# Baseline_Shield.net
KiCad netlist of a schematic drawn in EAGLE
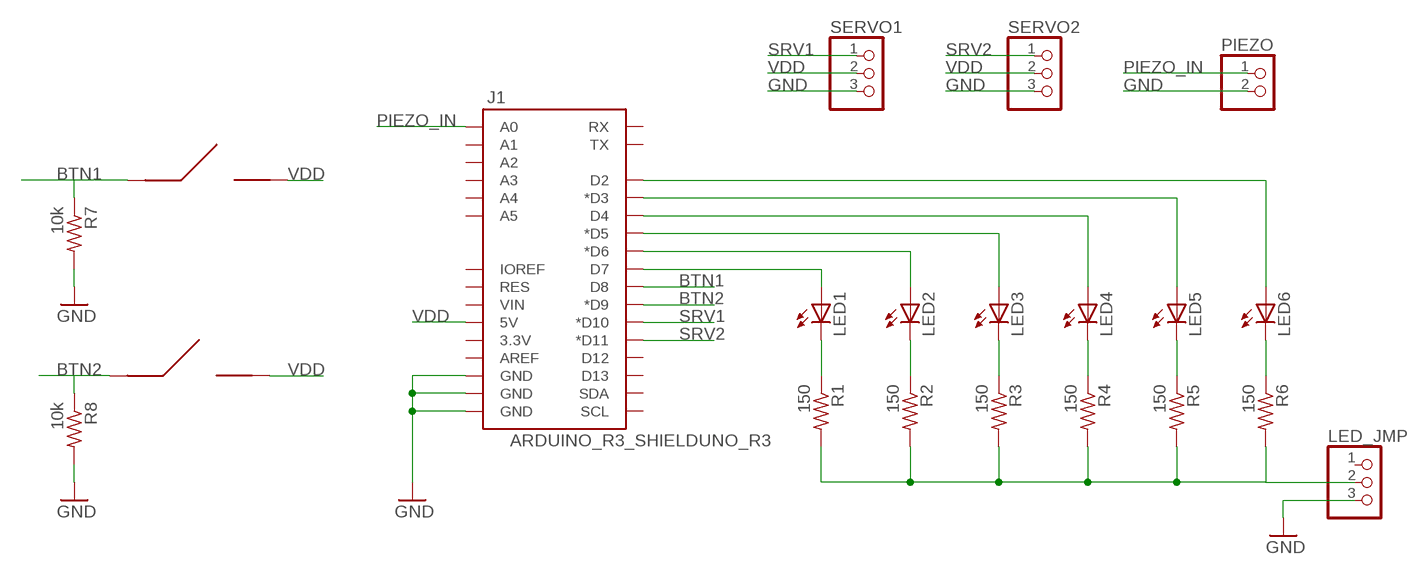
[diagram p0: schematic, sheet 1]

(export (version "E")
  (design (tool "Eeschema 10.0.6"))
  (components
    (comp (ref "J1")
      (value "ARDUINO_R3_SHIELDUNO_R3")
      (footprint "eagle-import:UNO_R3_SHIELD")
      (libsource (lib "eagle-import") (part "ARDUINO_R3_SHIELD"))
    )
    (comp (ref "LED1")
      (value "LEDCHIPLED_1206")
      (footprint "eagle-import:CHIPLED_1206")
      (libsource (lib "eagle-import") (part "LEDCHIPLED_1206"))
    )
    (comp (ref "LED2")
      (value "LEDCHIPLED_1206")
      (footprint "eagle-import:CHIPLED_1206")
      (libsource (lib "eagle-import") (part "LEDCHIPLED_1206"))
    )
    (comp (ref "LED3")
      (value "LEDCHIPLED_1206")
      (footprint "eagle-import:CHIPLED_1206")
      (libsource (lib "eagle-import") (part "LEDCHIPLED_1206"))
    )
    (comp (ref "LED4")
      (value "LEDCHIPLED_1206")
      (footprint "eagle-import:CHIPLED_1206")
      (libsource (lib "eagle-import") (part "LEDCHIPLED_1206"))
    )
    (comp (ref "LED5")
      (value "LEDCHIPLED_1206")
      (footprint "eagle-import:CHIPLED_1206")
      (libsource (lib "eagle-import") (part "LEDCHIPLED_1206"))
    )
    (comp (ref "LED6")
      (value "LEDCHIPLED_1206")
      (footprint "eagle-import:CHIPLED_1206")
      (libsource (lib "eagle-import") (part "LEDCHIPLED_1206"))
    )
    (comp (ref "LED_JMP")
      (value "PINHD-1X3")
      (footprint "eagle-import:1X03")
      (libsource (lib "eagle-import") (part "PINHD-1X3"))
    )
    (comp (ref "PIEZO")
      (value "PINHD-1X2")
      (footprint "eagle-import:1X02")
      (libsource (lib "eagle-import") (part "PINHD-1X2"))
    )
    (comp (ref "R1")
      (value "150")
      (footprint "eagle-import:R1206")
      (libsource (lib "eagle-import") (part "R-US_R1206"))
    )
    (comp (ref "R2")
      (value "150")
      (footprint "eagle-import:R1206")
      (libsource (lib "eagle-import") (part "R-US_R1206"))
    )
    (comp (ref "R3")
      (value "150")
      (footprint "eagle-import:R1206")
      (libsource (lib "eagle-import") (part "R-US_R1206"))
    )
    (comp (ref "R4")
      (value "150")
      (footprint "eagle-import:R1206")
      (libsource (lib "eagle-import") (part "R-US_R1206"))
    )
    (comp (ref "R5")
      (value "150")
      (footprint "eagle-import:R1206")
      (libsource (lib "eagle-import") (part "R-US_R1206"))
    )
    (comp (ref "R6")
      (value "150")
      (footprint "eagle-import:R1206")
      (libsource (lib "eagle-import") (part "R-US_R1206"))
    )
    (comp (ref "R7")
      (value "10k")
      (footprint "eagle-import:R1206")
      (libsource (lib "eagle-import") (part "R-US_R1206"))
    )
    (comp (ref "R8")
      (value "10k")
      (footprint "eagle-import:R1206")
      (libsource (lib "eagle-import") (part "R-US_R1206"))
    )
    (comp (ref "SERVO1")
      (value "PINHD-1X3")
      (footprint "eagle-import:1X03")
      (libsource (lib "eagle-import") (part "PINHD-1X3"))
    )
    (comp (ref "SERVO2")
      (value "PINHD-1X3")
      (footprint "eagle-import:1X03")
      (libsource (lib "eagle-import") (part "PINHD-1X3"))
    )
    (comp (ref "U$1")
      (value "IEEE_LOGO_BUTTON")
      (footprint "eagle-import:IEEE_LOGO_BUTTON")
      (libsource (lib "eagle-import") (part "IEEE_LOGO_BUTTON"))
    )
    (comp (ref "U$2")
      (value "IEEE_LOGO_BUTTON")
      (footprint "eagle-import:IEEE_LOGO_BUTTON")
      (libsource (lib "eagle-import") (part "IEEE_LOGO_BUTTON"))
    )
  )
  (nets
    (net (code "1") (name "/BTN1") (class "Default")
      (node (ref "J1") (pin "D8") (pinfunction "D8_D8") (pintype "bidirectional"))
      (node (ref "R7") (pin "1") (pinfunction "1_1") (pintype "passive"))
      (node (ref "U$2") (pin "P$1") (pinfunction "P$1_P$1") (pintype "bidirectional"))
    )
    (net (code "2") (name "/BTN2") (class "Default")
      (node (ref "J1") (pin "D9") (pinfunction "*D9_D9") (pintype "bidirectional"))
      (node (ref "R8") (pin "1") (pinfunction "1_1") (pintype "passive"))
      (node (ref "U$1") (pin "P$1") (pinfunction "P$1_P$1") (pintype "bidirectional"))
    )
    (net (code "3") (name "/PIEZO_IN") (class "Default")
      (node (ref "J1") (pin "A0") (pinfunction "A0_A0") (pintype "bidirectional"))
      (node (ref "PIEZO") (pin "1") (pinfunction "1_1") (pintype "passive"))
    )
    (net (code "4") (name "/SRV1") (class "Default")
      (node (ref "J1") (pin "D10") (pinfunction "*D10_D10") (pintype "bidirectional"))
      (node (ref "SERVO1") (pin "1") (pinfunction "1_1") (pintype "passive"))
    )
    (net (code "5") (name "/SRV2") (class "Default")
      (node (ref "J1") (pin "D11") (pinfunction "*D11_D11") (pintype "bidirectional"))
      (node (ref "SERVO2") (pin "1") (pinfunction "1_1") (pintype "passive"))
    )
    (net (code "6") (name "/VDD") (class "Default")
      (node (ref "J1") (pin "5V") (pinfunction "5V_5V") (pintype "bidirectional"))
      (node (ref "SERVO1") (pin "2") (pinfunction "2_2") (pintype "passive"))
      (node (ref "SERVO2") (pin "2") (pinfunction "2_2") (pintype "passive"))
      (node (ref "U$1") (pin "P$2") (pinfunction "P$2_P$2") (pintype "bidirectional"))
      (node (ref "U$2") (pin "P$2") (pinfunction "P$2_P$2") (pintype "bidirectional"))
    )
    (net (code "7") (name "GND") (class "Default")
      (node (ref "J1") (pin "GND@0") (pinfunction "GND_GND@0") (pintype "bidirectional"))
      (node (ref "J1") (pin "GND@1") (pinfunction "GND_GND@1") (pintype "bidirectional"))
      (node (ref "J1") (pin "GND@2") (pinfunction "GND_GND@2") (pintype "bidirectional"))
      (node (ref "LED_JMP") (pin "3") (pinfunction "3_3") (pintype "passive"))
      (node (ref "PIEZO") (pin "2") (pinfunction "2_2") (pintype "passive"))
      (node (ref "R7") (pin "2") (pinfunction "2_2") (pintype "passive"))
      (node (ref "R8") (pin "2") (pinfunction "2_2") (pintype "passive"))
      (node (ref "SERVO1") (pin "3") (pinfunction "3_3") (pintype "passive"))
      (node (ref "SERVO2") (pin "3") (pinfunction "3_3") (pintype "passive"))
    )
    (net (code "8") (name "Net-(J1-*D3)") (class "Default")
      (node (ref "J1") (pin "D3") (pinfunction "*D3_D3") (pintype "bidirectional"))
      (node (ref "LED5") (pin "A") (pinfunction "A_A") (pintype "passive"))
    )
    (net (code "9") (name "Net-(J1-*D5)") (class "Default")
      (node (ref "J1") (pin "D5") (pinfunction "*D5_D5") (pintype "bidirectional"))
      (node (ref "LED3") (pin "A") (pinfunction "A_A") (pintype "passive"))
    )
    (net (code "10") (name "Net-(J1-*D6)") (class "Default")
      (node (ref "J1") (pin "D6") (pinfunction "*D6_D6") (pintype "bidirectional"))
      (node (ref "LED2") (pin "A") (pinfunction "A_A") (pintype "passive"))
    )
    (net (code "11") (name "Net-(J1-PadD2)") (class "Default")
      (node (ref "J1") (pin "D2") (pinfunction "D2_D2") (pintype "bidirectional"))
      (node (ref "LED6") (pin "A") (pinfunction "A_A") (pintype "passive"))
    )
    (net (code "12") (name "Net-(J1-PadD4)") (class "Default")
      (node (ref "J1") (pin "D4") (pinfunction "D4_D4") (pintype "bidirectional"))
      (node (ref "LED4") (pin "A") (pinfunction "A_A") (pintype "passive"))
    )
    (net (code "13") (name "Net-(J1-PadD7)") (class "Default")
      (node (ref "J1") (pin "D7") (pinfunction "D7_D7") (pintype "bidirectional"))
      (node (ref "LED1") (pin "A") (pinfunction "A_A") (pintype "passive"))
    )
    (net (code "14") (name "Net-(LED1-PadC)") (class "Default")
      (node (ref "LED1") (pin "C") (pinfunction "C_C") (pintype "passive"))
      (node (ref "R1") (pin "1") (pinfunction "1_1") (pintype "passive"))
    )
    (net (code "15") (name "Net-(LED2-PadC)") (class "Default")
      (node (ref "LED2") (pin "C") (pinfunction "C_C") (pintype "passive"))
      (node (ref "R2") (pin "1") (pinfunction "1_1") (pintype "passive"))
    )
    (net (code "16") (name "Net-(LED3-PadC)") (class "Default")
      (node (ref "LED3") (pin "C") (pinfunction "C_C") (pintype "passive"))
      (node (ref "R3") (pin "1") (pinfunction "1_1") (pintype "passive"))
    )
    (net (code "17") (name "Net-(LED4-PadC)") (class "Default")
      (node (ref "LED4") (pin "C") (pinfunction "C_C") (pintype "passive"))
      (node (ref "R4") (pin "1") (pinfunction "1_1") (pintype "passive"))
    )
    (net (code "18") (name "Net-(LED5-PadC)") (class "Default")
      (node (ref "LED5") (pin "C") (pinfunction "C_C") (pintype "passive"))
      (node (ref "R5") (pin "1") (pinfunction "1_1") (pintype "passive"))
    )
    (net (code "19") (name "Net-(LED6-PadC)") (class "Default")
      (node (ref "LED6") (pin "C") (pinfunction "C_C") (pintype "passive"))
      (node (ref "R6") (pin "1") (pinfunction "1_1") (pintype "passive"))
    )
    (net (code "20") (name "Net-(LED_JMP-Pad2)") (class "Default")
      (node (ref "LED_JMP") (pin "2") (pinfunction "2_2") (pintype "passive"))
      (node (ref "R1") (pin "2") (pinfunction "2_2") (pintype "passive"))
      (node (ref "R2") (pin "2") (pinfunction "2_2") (pintype "passive"))
      (node (ref "R3") (pin "2") (pinfunction "2_2") (pintype "passive"))
      (node (ref "R4") (pin "2") (pinfunction "2_2") (pintype "passive"))
      (node (ref "R5") (pin "2") (pinfunction "2_2") (pintype "passive"))
      (node (ref "R6") (pin "2") (pinfunction "2_2") (pintype "passive"))
    )
    (net (code "21") (name "unconnected-(J1-Pad3.3V)") (class "Default")
      (node (ref "J1") (pin "3.3V") (pinfunction "3.3V_3.3V") (pintype "bidirectional"))
    )
    (net (code "22") (name "unconnected-(J1-PadA1)") (class "Default")
      (node (ref "J1") (pin "A1") (pinfunction "A1_A1") (pintype "bidirectional"))
    )
    (net (code "23") (name "unconnected-(J1-PadA2)") (class "Default")
      (node (ref "J1") (pin "A2") (pinfunction "A2_A2") (pintype "bidirectional"))
    )
    (net (code "24") (name "unconnected-(J1-PadA3)") (class "Default")
      (node (ref "J1") (pin "A3") (pinfunction "A3_A3") (pintype "bidirectional"))
    )
    (net (code "25") (name "unconnected-(J1-PadA4)") (class "Default")
      (node (ref "J1") (pin "A4") (pinfunction "A4_A4") (pintype "bidirectional"))
    )
    (net (code "26") (name "unconnected-(J1-PadA5)") (class "Default")
      (node (ref "J1") (pin "A5") (pinfunction "A5_A5") (pintype "bidirectional"))
    )
    (net (code "27") (name "unconnected-(J1-PadAREF)") (class "Default")
      (node (ref "J1") (pin "AREF") (pinfunction "AREF_AREF") (pintype "bidirectional"))
    )
    (net (code "28") (name "unconnected-(J1-PadD12)") (class "Default")
      (node (ref "J1") (pin "D12") (pinfunction "D12_D12") (pintype "bidirectional"))
    )
    (net (code "29") (name "unconnected-(J1-PadD13)") (class "Default")
      (node (ref "J1") (pin "D13") (pinfunction "D13_D13") (pintype "bidirectional"))
    )
    (net (code "30") (name "unconnected-(J1-PadIOREF)") (class "Default")
      (node (ref "J1") (pin "IOREF") (pinfunction "IOREF_IOREF") (pintype "bidirectional"))
    )
    (net (code "31") (name "unconnected-(J1-PadRES)") (class "Default")
      (node (ref "J1") (pin "RES") (pinfunction "RES_RES") (pintype "bidirectional"))
    )
    (net (code "32") (name "unconnected-(J1-PadRX)") (class "Default")
      (node (ref "J1") (pin "RX") (pinfunction "RX_RX") (pintype "bidirectional"))
    )
    (net (code "33") (name "unconnected-(J1-PadSCL)") (class "Default")
      (node (ref "J1") (pin "SCL") (pinfunction "SCL_SCL") (pintype "bidirectional"))
    )
    (net (code "34") (name "unconnected-(J1-PadSDA)") (class "Default")
      (node (ref "J1") (pin "SDA") (pinfunction "SDA_SDA") (pintype "bidirectional"))
    )
    (net (code "35") (name "unconnected-(J1-PadTX)") (class "Default")
      (node (ref "J1") (pin "TX") (pinfunction "TX_TX") (pintype "bidirectional"))
    )
    (net (code "36") (name "unconnected-(J1-PadVIN)") (class "Default")
      (node (ref "J1") (pin "VIN") (pinfunction "VIN_VIN") (pintype "bidirectional"))
    )
    (net (code "37") (name "unconnected-(LED_JMP-Pad1)") (class "Default")
      (node (ref "LED_JMP") (pin "1") (pinfunction "1_1") (pintype "passive"))
    )
  )
)
